# RaceDAQ_IN_OUT.net
KiCad netlist of a schematic drawn in Altium Designer
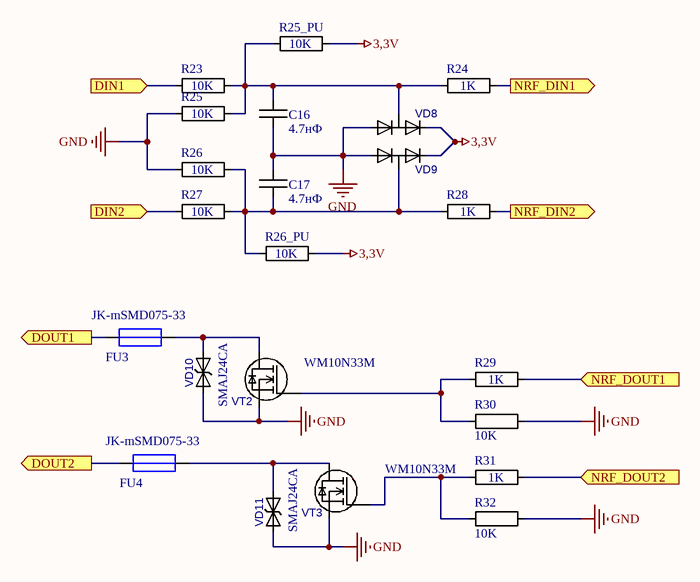
[diagram p0: RaceDAQ_IN_OUT.SchDoc]

(export (version "E")
  (design (tool "Eeschema 10.0.6"))
  (components
    (comp (ref "C16") (value "4.7нФ") (footprint "CAPC1608X90L25N") (libsource (lib "tlib") (part "CAP")))
    (comp (ref "C17") (value "4.7нФ") (footprint "CAPC1608X90L25N") (libsource (lib "tlib") (part "CAP")))
    (comp (ref "FU3")
      (value "JK-mSMD075-33")
      (footprint "FUSE: 1812")
      (description "Предохраниетель ток срабатывания 1,5А, ток удержания 750мА")
      (libsource (lib "Fuse") (part "JK-mSMD075-33"))
    )
    (comp (ref "FU4")
      (value "JK-mSMD075-33")
      (footprint "FUSE: 1812")
      (description "Предохраниетель ток срабатывания 1,5А, ток удержания 750мА")
      (libsource (lib "Fuse") (part "JK-mSMD075-33"))
    )
    (comp (ref "R23") (value "10K") (footprint "RESC2012X60L35N") (libsource (lib "tlib") (part "RES")))
    (comp (ref "R24") (value "1K") (footprint "RESC1608X55L25N") (libsource (lib "tlib") (part "RES")))
    (comp (ref "R25") (value "10K") (footprint "RESC2012X60L35N") (libsource (lib "tlib") (part "RES")))
    (comp (ref "R25_PU") (value "10K") (footprint "RESC2012X60L35N") (libsource (lib "tlib") (part "RES")))
    (comp (ref "R26") (value "10K") (footprint "RESC2012X60L35N") (libsource (lib "tlib") (part "RES")))
    (comp (ref "R26_PU") (value "10K") (footprint "RESC2012X60L35N") (libsource (lib "tlib") (part "RES")))
    (comp (ref "R27") (value "10K") (footprint "RESC2012X60L35N") (libsource (lib "tlib") (part "RES")))
    (comp (ref "R28") (value "1K") (footprint "RESC1608X55L25N") (libsource (lib "tlib") (part "RES")))
    (comp (ref "R29") (value "1K") (footprint "RESC1608X55L25N") (libsource (lib "tlib") (part "RES")))
    (comp (ref "R30") (value "10K") (footprint "RESC2012X60L35N") (libsource (lib "tlib") (part "RES")))
    (comp (ref "R31") (value "1K") (footprint "RESC1608X55L25N") (libsource (lib "tlib") (part "RES")))
    (comp (ref "R32") (value "10K") (footprint "RESC2012X60L35N") (libsource (lib "tlib") (part "RES")))
    (comp (ref "VD8")
      (value "BAT54S")
      (footprint "SOT95P240X110-3L16")
      (libsource (lib "tlib") (part "BAT54S"))
    )
    (comp (ref "VD9")
      (value "BAT54S")
      (footprint "SOT95P240X110-3L16")
      (libsource (lib "tlib") (part "BAT54S"))
    )
    (comp (ref "VD10")
      (value "SMAJ24CA")
      (footprint "DIOM5126X229")
      (libsource (lib "tlib") (part "TVSBI_AC"))
    )
    (comp (ref "VD11")
      (value "SMAJ24CA")
      (footprint "DIOM5126X229")
      (libsource (lib "tlib") (part "TVSBI_AC"))
    )
    (comp (ref "VT2")
      (value "WM10N33M")
      (footprint "SOT95P240X110-3L10")
      (libsource (lib "tlib") (part "NMOSFET_GSD"))
    )
    (comp (ref "VT3")
      (value "WM10N33M")
      (footprint "SOT95P240X110-3L10")
      (libsource (lib "tlib") (part "NMOSFET_GSD"))
    )
  )
  (nets
    (net (code "1") (name "/DIN1") (class "Default")
      (node (ref "R23") (pin "1") (pinfunction "1_1") (pintype "passive"))
    )
    (net (code "2") (name "/DIN2") (class "Default")
      (node (ref "R27") (pin "1") (pinfunction "1_1") (pintype "passive"))
    )
    (net (code "3") (name "/DOUT1") (class "Default")
      (node (ref "FU3") (pin "1") (pinfunction "1_1") (pintype "passive"))
    )
    (net (code "4") (name "/DOUT2") (class "Default")
      (node (ref "FU4") (pin "1") (pinfunction "1_1") (pintype "passive"))
    )
    (net (code "5") (name "/NRF_DIN1") (class "Default")
      (node (ref "R24") (pin "2") (pinfunction "2_2") (pintype "passive"))
    )
    (net (code "6") (name "/NRF_DIN2") (class "Default")
      (node (ref "R28") (pin "2") (pinfunction "2_2") (pintype "passive"))
    )
    (net (code "7") (name "/NRF_DOUT1") (class "Default")
      (node (ref "R29") (pin "2") (pinfunction "2_2") (pintype "passive"))
    )
    (net (code "8") (name "/NRF_DOUT2") (class "Default")
      (node (ref "R31") (pin "2") (pinfunction "2_2") (pintype "passive"))
    )
    (net (code "9") (name "3,3V") (class "Default")
      (node (ref "R25_PU") (pin "1") (pinfunction "1_1") (pintype "passive"))
      (node (ref "R26_PU") (pin "1") (pinfunction "1_1") (pintype "passive"))
      (node (ref "VD8") (pin "2") (pintype "passive"))
      (node (ref "VD9") (pin "2") (pintype "passive"))
    )
    (net (code "10") (name "GND") (class "Default")
      (node (ref "C16") (pin "1") (pintype "passive"))
      (node (ref "C17") (pin "2") (pintype "passive"))
      (node (ref "R25") (pin "2") (pinfunction "2_2") (pintype "passive"))
      (node (ref "R26") (pin "1") (pinfunction "1_1") (pintype "passive"))
      (node (ref "R30") (pin "1") (pinfunction "1_1") (pintype "passive"))
      (node (ref "R32") (pin "1") (pinfunction "1_1") (pintype "passive"))
      (node (ref "VD10") (pin "A") (pintype "passive"))
      (node (ref "VD11") (pin "A") (pintype "passive"))
      (node (ref "VD8") (pin "1") (pintype "passive"))
      (node (ref "VD9") (pin "1") (pintype "passive"))
      (node (ref "VT2") (pin "2") (pintype "passive"))
      (node (ref "VT3") (pin "2") (pintype "passive"))
    )
    (net (code "11") (name "Net-(C16-Pad2)") (class "Default")
      (node (ref "C16") (pin "2") (pintype "passive"))
      (node (ref "R23") (pin "2") (pinfunction "2_2") (pintype "passive"))
      (node (ref "R24") (pin "1") (pinfunction "1_1") (pintype "passive"))
      (node (ref "R25") (pin "1") (pinfunction "1_1") (pintype "passive"))
      (node (ref "R25_PU") (pin "2") (pinfunction "2_2") (pintype "passive"))
      (node (ref "VD8") (pin "3") (pintype "passive"))
    )
    (net (code "12") (name "Net-(C17-Pad1)") (class "Default")
      (node (ref "C17") (pin "1") (pintype "passive"))
      (node (ref "R26") (pin "2") (pinfunction "2_2") (pintype "passive"))
      (node (ref "R26_PU") (pin "2") (pinfunction "2_2") (pintype "passive"))
      (node (ref "R27") (pin "2") (pinfunction "2_2") (pintype "passive"))
      (node (ref "R28") (pin "1") (pinfunction "1_1") (pintype "passive"))
      (node (ref "VD9") (pin "3") (pintype "passive"))
    )
    (net (code "13") (name "Net-(FU3-Pad2)") (class "Default")
      (node (ref "FU3") (pin "2") (pinfunction "2_2") (pintype "passive"))
      (node (ref "VD10") (pin "C") (pintype "passive"))
      (node (ref "VT2") (pin "3") (pintype "passive"))
    )
    (net (code "14") (name "Net-(FU4-Pad2)") (class "Default")
      (node (ref "FU4") (pin "2") (pinfunction "2_2") (pintype "passive"))
      (node (ref "VD11") (pin "C") (pintype "passive"))
      (node (ref "VT3") (pin "3") (pintype "passive"))
    )
    (net (code "15") (name "Net-(R29-Pad1)") (class "Default")
      (node (ref "R29") (pin "1") (pinfunction "1_1") (pintype "passive"))
      (node (ref "R30") (pin "2") (pinfunction "2_2") (pintype "passive"))
      (node (ref "VT2") (pin "1") (pintype "passive"))
    )
    (net (code "16") (name "Net-(R31-Pad1)") (class "Default")
      (node (ref "R31") (pin "1") (pinfunction "1_1") (pintype "passive"))
      (node (ref "R32") (pin "2") (pinfunction "2_2") (pintype "passive"))
      (node (ref "VT3") (pin "1") (pintype "passive"))
    )
  )
)
